# ZeroCrossSimple.net
KiCad netlist of a schematic drawn in EAGLE
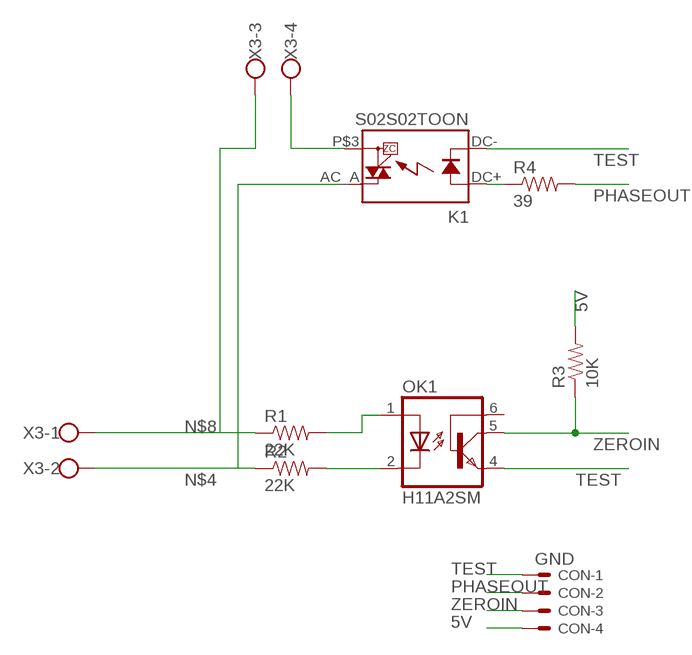
[diagram p0: schematic, sheet 1]

(export (version "E")
  (design (tool "Eeschema 10.0.6"))
  (components
    (comp (ref "CON")
      (value "GND")
      (footprint "eagle-import:KK-156-4")
      (libsource (lib "eagle-import") (part "KK-156-4"))
    )
    (comp (ref "K1")
      (value "S02S02TOON")
      (footprint "eagle-import:TOON")
      (libsource (lib "eagle-import") (part "S02S02TOON"))
    )
    (comp (ref "OK1")
      (value "H11A2SM")
      (footprint "eagle-import:DIL6-SMD")
      (libsource (lib "eagle-import") (part "H11A?MS2"))
    )
    (comp (ref "R1")
      (value "22K")
      (footprint "eagle-import:R2512")
      (libsource (lib "eagle-import") (part "RESISTOR2512"))
    )
    (comp (ref "R2")
      (value "22K")
      (footprint "eagle-import:R2512")
      (libsource (lib "eagle-import") (part "RESISTOR2512"))
    )
    (comp (ref "R3")
      (value "10K")
      (footprint "eagle-import:0805")
      (libsource (lib "eagle-import") (part "RESISTOR0805-RES"))
    )
    (comp (ref "R4")
      (value "39")
      (footprint "eagle-import:0805")
      (libsource (lib "eagle-import") (part "SparkFun-Resistors_RESISTOR0805-RES"))
    )
    (comp (ref "X3")
      (value "W237-4")
      (footprint "eagle-import:W237-4")
      (libsource (lib "eagle-import") (part "W237-4"))
    )
  )
  (nets
    (net (code "1") (name "/5V") (class "Default")
      (node (ref "CON") (pin "4") (pinfunction "S_4") (pintype "passive"))
      (node (ref "R3") (pin "2") (pinfunction "2_2") (pintype "passive"))
    )
    (net (code "2") (name "/N$4") (class "Default")
      (node (ref "K1") (pin "AC_A") (pinfunction "DS1_AC_A") (pintype "passive"))
      (node (ref "R2") (pin "1") (pinfunction "1_1") (pintype "passive"))
      (node (ref "X3") (pin "2") (pinfunction "KL_2") (pintype "passive"))
    )
    (net (code "3") (name "/N$8") (class "Default")
      (node (ref "R1") (pin "1") (pinfunction "1_1") (pintype "passive"))
      (node (ref "X3") (pin "1") (pinfunction "KL_1") (pintype "passive"))
      (node (ref "X3") (pin "3") (pinfunction "KL_3") (pintype "passive"))
    )
    (net (code "4") (name "/PHASEOUT") (class "Default")
      (node (ref "CON") (pin "2") (pinfunction "S_2") (pintype "passive"))
      (node (ref "R4") (pin "2") (pinfunction "2_2") (pintype "passive"))
    )
    (net (code "5") (name "/TEST") (class "Default")
      (node (ref "CON") (pin "1") (pinfunction "S_1") (pintype "passive"))
      (node (ref "K1") (pin "DC-") (pinfunction "K_DC-") (pintype "passive"))
      (node (ref "OK1") (pin "4") (pinfunction "EMI_4") (pintype "passive"))
    )
    (net (code "6") (name "/ZEROIN") (class "Default")
      (node (ref "CON") (pin "3") (pinfunction "S_3") (pintype "passive"))
      (node (ref "OK1") (pin "5") (pinfunction "COL_5") (pintype "passive"))
      (node (ref "R3") (pin "1") (pinfunction "1_1") (pintype "passive"))
    )
    (net (code "7") (name "Net-(K1-A)") (class "Default")
      (node (ref "K1") (pin "DC+") (pinfunction "A_DC+") (pintype "passive"))
      (node (ref "R4") (pin "1") (pinfunction "1_1") (pintype "passive"))
    )
    (net (code "8") (name "Net-(K1-DS2)") (class "Default")
      (node (ref "K1") (pin "P$3") (pinfunction "DS2_P$3") (pintype "passive"))
      (node (ref "X3") (pin "4") (pinfunction "KL_4") (pintype "passive"))
    )
    (net (code "9") (name "Net-(OK1-A)") (class "Default")
      (node (ref "OK1") (pin "1") (pinfunction "A_1") (pintype "passive"))
      (node (ref "R1") (pin "2") (pinfunction "2_2") (pintype "passive"))
    )
    (net (code "10") (name "Net-(OK1-C)") (class "Default")
      (node (ref "OK1") (pin "2") (pinfunction "C_2") (pintype "passive"))
      (node (ref "R2") (pin "2") (pinfunction "2_2") (pintype "passive"))
    )
    (net (code "11") (name "unconnected-(OK1-BAS-Pad6)") (class "Default")
      (node (ref "OK1") (pin "6") (pinfunction "BAS_6") (pintype "passive"))
    )
  )
)
